# Boostconverter.net
KiCad netlist of a schematic drawn in Altium Designer
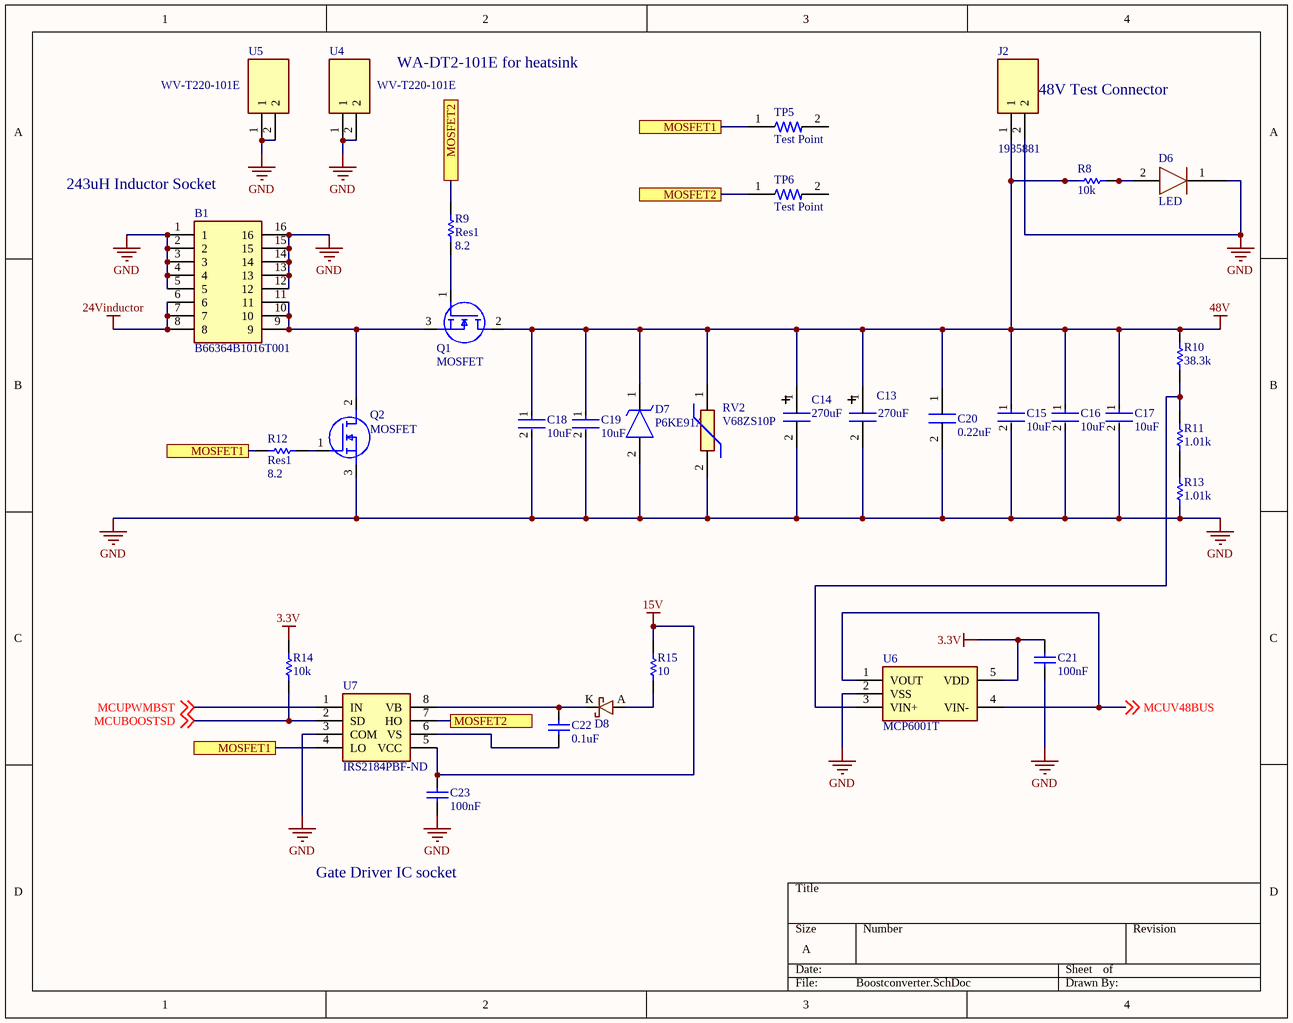
[diagram p0: Boostconverter.SchDoc]

(export (version "E")
  (design (tool "Eeschema 10.0.6"))
  (components
    (comp (ref "B1")
      (value "B66364B1016T001")
      (footprint "B66364B1016T001")
      (description "Bobbin")
      (fields (field (name "MOUSER2 PART NUMBER") "871-B66364B1016T001"))
      (libsource (lib "ee_453_yourname") (part "B66364B1016T001"))
    )
    (comp (ref "C13")
      (value "270uF")
      (footprint "100TXW270MEFC10X50")
      (description "Capacitor, 10mm, 5mm leads")
      (libsource (lib "ee_453_yourname") (part "100TXW270MEFC10X50"))
    )
    (comp (ref "C14")
      (value "270uF")
      (footprint "100TXW270MEFC10X50")
      (description "Capacitor, 10mm, 5mm leads")
      (libsource (lib "ee_453_yourname") (part "100TXW270MEFC10X50"))
    )
    (comp (ref "C15")
      (value "10uF")
      (footprint "FP-CL31-IPC_C")
      (description "Cap Ceramic 220pF 500V C0G ±5% SMD 1206 +125°C Embossed T/R CL31C221JGFNNNF")
      (fields (field (name "TOLERANCE") "5%"))
      (libsource (lib "Altium Content Vault") (part "b4654b650e69147ec39a6b967a45e02"))
    )
    (comp (ref "C16")
      (value "10uF")
      (footprint "FP-CL31-IPC_C")
      (description "Cap Ceramic 220pF 500V C0G ±5% SMD 1206 +125°C Embossed T/R CL31C221JGFNNNF")
      (fields (field (name "TOLERANCE") "5%"))
      (libsource (lib "Altium Content Vault") (part "b4654b650e69147ec39a6b967a45e02"))
    )
    (comp (ref "C17")
      (value "10uF")
      (footprint "FP-CL31-IPC_C")
      (description "Cap Ceramic 220pF 500V C0G ±5% SMD 1206 +125°C Embossed T/R CL31C221JGFNNNF")
      (fields (field (name "TOLERANCE") "5%"))
      (libsource (lib "Altium Content Vault") (part "b4654b650e69147ec39a6b967a45e02"))
    )
    (comp (ref "C18")
      (value "10uF")
      (footprint "FP-CL31-IPC_C")
      (description "Cap Ceramic 220pF 500V C0G ±5% SMD 1206 +125°C Embossed T/R CL31C221JGFNNNF")
      (fields (field (name "TOLERANCE") "5%"))
      (libsource (lib "Altium Content Vault") (part "b4654b650e69147ec39a6b967a45e02"))
    )
    (comp (ref "C19")
      (value "10uF")
      (footprint "FP-CL31-IPC_C")
      (description "Cap Ceramic 220pF 500V C0G ±5% SMD 1206 +125°C Embossed T/R CL31C221JGFNNNF")
      (fields (field (name "TOLERANCE") "5%"))
      (libsource (lib "Altium Content Vault") (part "b4654b650e69147ec39a6b967a45e02"))
    )
    (comp (ref "C20")
      (value "0.22uF")
      (footprint "B32652A3224K000")
      (description "Capacitor, Film, 15mm leads")
      (libsource (lib "ee_453_yourname") (part "B32652A3224K000"))
    )
    (comp (ref "C21")
      (value "100nF")
      (footprint "CAPC1609X100X15LL20")
      (fields
        (field (name "MANUFACTURER") "AVX Interconnect / Elco")
        (field (name "PART NUMBER") "TACL105M006XTA")
      )
      (libsource (lib "Altium Content Vault") (part "CAP"))
    )
    (comp (ref "C22")
      (value "0.1uF")
      (footprint "CAPC1609X100X15LL20")
      (fields
        (field (name "MANUFACTURER") "AVX Interconnect / Elco")
        (field (name "PART NUMBER") "TACL105M006XTA")
      )
      (libsource (lib "Altium Content Vault") (part "CAP"))
    )
    (comp (ref "C23")
      (value "100nF")
      (footprint "CAPC1609X100X15LL20")
      (fields
        (field (name "MANUFACTURER") "AVX Interconnect / Elco")
        (field (name "PART NUMBER") "TACL105M006XTA")
      )
      (libsource (lib "Altium Content Vault") (part "CAP"))
    )
    (comp (ref "D6")
      (value "LED")
      (footprint "LED 0603")
      (description "LED SMD")
      (libsource (lib "ee_453_yourname") (part "LED"))
    )
    (comp (ref "D7")
      (value "P6KE91A")
      (footprint "SamacSys:DIOAD1910W86L670D310")
      (description "TVS Diode (Uni-directional)")
      (fields (field (name "MANUFACTURER_PART_NUMBER") "P6KE91A-E3/54"))
      (libsource (lib "*") (part "P6KE91A-E3_54"))
    )
    (comp (ref "D8")
      (value "SB3H100-E3_54")
      (footprint "SB3H100-E3/54GICT-ND")
      (description "Schottky Diode")
      (libsource (lib "ee_453_yourname") (part "SB3H100-E3_54"))
    )
    (comp (ref "J2")
      (value "1985881")
      (footprint "SamacSys:1985881")
      (description "Connector")
      (fields (field (name "MOUSER PART NUMBER") "651-1985881"))
      (libsource (lib "*") (part "1985881"))
    )
    (comp (ref "Q1")
      (value "MOSFET")
      (footprint "SamacSys:TO254P457X1003X2115-3P")
      (description "MOSFET (N-Channel) IPP200N15N3GXKSA1")
      (fields
        (field (name "MANUFACTURER_PART_NUMBER") "IPP200N15N3GXKSA1")
        (field (name "MOUSER PART NUMBER") "726-IPP200N15N3GXKSA")
      )
      (libsource (lib "*") (part "IPP200N15N3GXKSA1"))
    )
    (comp (ref "Q2")
      (value "MOSFET")
      (footprint "SamacSys:TO254P457X1003X2115-3P")
      (description "MOSFET (N-Channel) IPP200N15N3GXKSA1")
      (fields
        (field (name "MANUFACTURER_PART_NUMBER") "IPP200N15N3GXKSA1")
        (field (name "MOUSER PART NUMBER") "726-IPP200N15N3GXKSA")
      )
      (libsource (lib "*") (part "IPP200N15N3GXKSA1"))
    )
    (comp (ref "R8")
      (value "10k")
      (footprint "RESC1609X50X30NL8T20")
      (description "Chip Resistor, 0 Ohm, Jumper, 100 mW, -55 to 155 degC, 0603 (1608 Metric), RoHS, Tape and Reel")
      (fields (field (name "MANUFACTURER") "Vishay Semiconductor"))
      (libsource (lib "Altium Content Vault") (part "RES-2"))
    )
    (comp (ref "R9")
      (value "Res1")
      (footprint "1210")
      (description "Resistor")
      (fields (field (name "ALTIUM_VALUE") "8.2") (field (name "PUBLISHER") "Altium Limited"))
      (libsource (lib "Miscellaneous Devices") (part "Res1"))
    )
    (comp (ref "R10")
      (value "38.3k")
      (footprint "RESC1609X50X30NL8T20")
      (description "Chip Resistor, 0 Ohm, Jumper, 100 mW, -55 to 155 degC, 0603 (1608 Metric), RoHS, Tape and Reel")
      (fields (field (name "MANUFACTURER") "Vishay Semiconductor"))
      (libsource (lib "Altium Content Vault") (part "RES-2"))
    )
    (comp (ref "R11")
      (value "1.01k")
      (footprint "RESC1609X50X30NL8T20")
      (description "Chip Resistor, 0 Ohm, Jumper, 100 mW, -55 to 155 degC, 0603 (1608 Metric), RoHS, Tape and Reel")
      (fields (field (name "MANUFACTURER") "Vishay Semiconductor"))
      (libsource (lib "Altium Content Vault") (part "RES-2"))
    )
    (comp (ref "R12")
      (value "Res1")
      (footprint "1210")
      (description "Resistor")
      (fields (field (name "ALTIUM_VALUE") "8.2") (field (name "PUBLISHER") "Altium Limited"))
      (libsource (lib "Miscellaneous Devices") (part "Res1"))
    )
    (comp (ref "R13")
      (value "1.01k")
      (footprint "RESC1609X50X30NL8T20")
      (description "Chip Resistor, 0 Ohm, Jumper, 100 mW, -55 to 155 degC, 0603 (1608 Metric), RoHS, Tape and Reel")
      (fields (field (name "MANUFACTURER") "Vishay Semiconductor"))
      (libsource (lib "Altium Content Vault") (part "RES-2"))
    )
    (comp (ref "R14")
      (value "10k")
      (footprint "RESC1609X50X30NL8T20")
      (description "Chip Resistor, 0 Ohm, Jumper, 100 mW, -55 to 155 degC, 0603 (1608 Metric), RoHS, Tape and Reel")
      (fields (field (name "MANUFACTURER") "Vishay Semiconductor"))
      (libsource (lib "Altium Content Vault") (part "RES-2"))
    )
    (comp (ref "R15")
      (value "10")
      (footprint "RESC1609X50X30NL8T20")
      (description "Chip Resistor, 0 Ohm, Jumper, 100 mW, -55 to 155 degC, 0603 (1608 Metric), RoHS, Tape and Reel")
      (fields (field (name "MANUFACTURER") "Vishay Semiconductor"))
      (libsource (lib "Altium Content Vault") (part "RES-2"))
    )
    (comp (ref "RV2")
      (value "V68ZS10P")
      (footprint "SamacSys:V68ZS10P")
      (description "Varistor")
      (fields (field (name "MOUSER PART NUMBER") "576-V68ZS10P"))
      (libsource (lib "*") (part "V68ZS10P"))
    )
    (comp (ref "TP5")
      (value "Test Point")
      (footprint "RESC3216X70N")
      (description "PC Test Point , Plating Surface Mount Mounting Type")
      (fields (field (name "MF") "KOA Speer") (field (name "MP") "RCWCTE"))
      (libsource (lib "SnapEDAsch") (part "RCWCTE"))
    )
    (comp (ref "TP6")
      (value "Test Point")
      (footprint "RESC3216X70N")
      (description "PC Test Point , Plating Surface Mount Mounting Type")
      (fields (field (name "MF") "KOA Speer") (field (name "MP") "RCWCTE"))
      (libsource (lib "SnapEDAsch") (part "RCWCTE"))
    )
    (comp (ref "U4")
      (value "WV-T220-101E")
      (footprint "SamacSys:WVT220101E")
      (description "Undefined or Miscellaneous")
      (fields (field (name "MOUSER PART NUMBER") "588-WV-T220-101E"))
      (libsource (lib "*") (part "WV-T220-101E"))
    )
    (comp (ref "U5")
      (value "WV-T220-101E")
      (footprint "SamacSys:WVT220101E")
      (description "Undefined or Miscellaneous")
      (fields (field (name "MOUSER PART NUMBER") "588-WV-T220-101E"))
      (libsource (lib "*") (part "WV-T220-101E"))
    )
    (comp (ref "U6")
      (value "MCP6001T")
      (footprint "SOT-23")
      (description "Op-Amp")
      (libsource (lib "ee_453_yourname") (part "MCP6001T"))
    )
    (comp (ref "U7")
      (value "IRS2184PBF-ND")
      (footprint "DIP8")
      (description "Boost Driver")
      (fields
        (field (name "MOUSER2 PART NUMBER") "649-DILB8P223TLF")
        (field (name "MANUFACTURER_PART_NUMBER") "DILB8P-223TLF")
      )
      (libsource (lib "ee_453_yourname") (part "IRS2184PBF-ND"))
    )
  )
  (nets
    (net (code "1") (name "/MOSFET1") (class "Default")
      (node (ref "R12") (pin "2") (pinfunction "2_2") (pintype "passive"))
      (node (ref "TP5") (pin "1") (pinfunction "1_1") (pintype "passive"))
      (node (ref "U7") (pin "4") (pinfunction "LO_4") (pintype "passive"))
    )
    (net (code "2") (name "/MOSFET2") (class "Default")
      (node (ref "R9") (pin "2") (pinfunction "2_2") (pintype "passive"))
      (node (ref "TP6") (pin "1") (pinfunction "1_1") (pintype "passive"))
      (node (ref "U7") (pin "7") (pinfunction "HO_7") (pintype "passive"))
    )
    (net (code "3") (name "3.3V") (class "Default")
      (node (ref "C21") (pin "1") (pinfunction "1_1") (pintype "passive"))
      (node (ref "R14") (pin "2") (pinfunction "2_2") (pintype "passive"))
      (node (ref "U6") (pin "5") (pinfunction "VDD_5") (pintype "passive"))
    )
    (net (code "4") (name "15V") (class "Default")
      (node (ref "C23") (pin "2") (pinfunction "2_2") (pintype "passive"))
      (node (ref "R15") (pin "2") (pinfunction "2_2") (pintype "passive"))
      (node (ref "U7") (pin "5") (pinfunction "VCC_5") (pintype "passive"))
    )
    (net (code "5") (name "24Vinductor") (class "Default")
      (node (ref "B1") (pin "6") (pinfunction "6_6") (pintype "passive"))
      (node (ref "B1") (pin "7") (pinfunction "7_7") (pintype "passive"))
      (node (ref "B1") (pin "8") (pinfunction "8_8") (pintype "passive"))
    )
    (net (code "6") (name "48V") (class "Default")
      (node (ref "C13") (pin "1") (pintype "passive"))
      (node (ref "C14") (pin "1") (pintype "passive"))
      (node (ref "C15") (pin "1") (pinfunction "1_1") (pintype "passive"))
      (node (ref "C16") (pin "1") (pinfunction "1_1") (pintype "passive"))
      (node (ref "C17") (pin "1") (pinfunction "1_1") (pintype "passive"))
      (node (ref "C18") (pin "1") (pinfunction "1_1") (pintype "passive"))
      (node (ref "C19") (pin "1") (pinfunction "1_1") (pintype "passive"))
      (node (ref "C20") (pin "1") (pintype "passive"))
      (node (ref "D7") (pin "1") (pinfunction "K_1") (pintype "passive"))
      (node (ref "J2") (pin "1") (pinfunction "1_1") (pintype "passive"))
      (node (ref "Q1") (pin "2") (pinfunction "D_2") (pintype "passive"))
      (node (ref "R10") (pin "2") (pinfunction "2_2") (pintype "passive"))
      (node (ref "R8") (pin "1") (pinfunction "1_1") (pintype "passive"))
      (node (ref "RV2") (pin "1") (pinfunction "1_1") (pintype "passive"))
    )
    (net (code "7") (name "GND") (class "Default")
      (node (ref "B1") (pin "1") (pinfunction "1_1") (pintype "passive"))
      (node (ref "B1") (pin "12") (pinfunction "12_12") (pintype "passive"))
      (node (ref "B1") (pin "13") (pinfunction "13_13") (pintype "passive"))
      (node (ref "B1") (pin "14") (pinfunction "14_14") (pintype "passive"))
      (node (ref "B1") (pin "15") (pinfunction "15_15") (pintype "passive"))
      (node (ref "B1") (pin "16") (pinfunction "16_16") (pintype "passive"))
      (node (ref "B1") (pin "2") (pinfunction "2_2") (pintype "passive"))
      (node (ref "B1") (pin "3") (pinfunction "3_3") (pintype "passive"))
      (node (ref "B1") (pin "4") (pinfunction "4_4") (pintype "passive"))
      (node (ref "B1") (pin "5") (pinfunction "5_5") (pintype "passive"))
      (node (ref "C13") (pin "2") (pintype "passive"))
      (node (ref "C14") (pin "2") (pintype "passive"))
      (node (ref "C15") (pin "2") (pinfunction "2_2") (pintype "passive"))
      (node (ref "C16") (pin "2") (pinfunction "2_2") (pintype "passive"))
      (node (ref "C17") (pin "2") (pinfunction "2_2") (pintype "passive"))
      (node (ref "C18") (pin "2") (pinfunction "2_2") (pintype "passive"))
      (node (ref "C19") (pin "2") (pinfunction "2_2") (pintype "passive"))
      (node (ref "C20") (pin "2") (pintype "passive"))
      (node (ref "C21") (pin "2") (pinfunction "2_2") (pintype "passive"))
      (node (ref "C23") (pin "1") (pinfunction "1_1") (pintype "passive"))
      (node (ref "D6") (pin "1") (pintype "passive"))
      (node (ref "D7") (pin "2") (pinfunction "A_2") (pintype "passive"))
      (node (ref "J2") (pin "2") (pinfunction "2_2") (pintype "passive"))
      (node (ref "Q2") (pin "3") (pinfunction "S_3") (pintype "passive"))
      (node (ref "R13") (pin "1") (pinfunction "1_1") (pintype "passive"))
      (node (ref "RV2") (pin "2") (pinfunction "2_2") (pintype "passive"))
      (node (ref "U4") (pin "1") (pinfunction "1_1") (pintype "passive"))
      (node (ref "U4") (pin "2") (pinfunction "2_2") (pintype "passive"))
      (node (ref "U5") (pin "1") (pinfunction "1_1") (pintype "passive"))
      (node (ref "U5") (pin "2") (pinfunction "2_2") (pintype "passive"))
      (node (ref "U6") (pin "2") (pinfunction "VSS_2") (pintype "passive"))
      (node (ref "U7") (pin "3") (pinfunction "COM_3") (pintype "passive"))
    )
    (net (code "8") (name "MCUBOOSTSD") (class "Default")
      (node (ref "R14") (pin "1") (pinfunction "1_1") (pintype "passive"))
      (node (ref "U7") (pin "2") (pinfunction "SD_2") (pintype "passive"))
    )
    (net (code "9") (name "MCUPWMBST") (class "Default")
      (node (ref "U7") (pin "1") (pinfunction "IN_1") (pintype "passive"))
    )
    (net (code "10") (name "MCUV48BUS") (class "Default")
      (node (ref "U6") (pin "1") (pinfunction "VOUT_1") (pintype "passive"))
      (node (ref "U6") (pin "4") (pinfunction "VIN-_4") (pintype "passive"))
    )
    (net (code "11") (name "Net-(D6-Pad2)") (class "Default")
      (node (ref "D6") (pin "2") (pintype "passive"))
      (node (ref "R8") (pin "2") (pinfunction "2_2") (pintype "passive"))
    )
    (net (code "12") (name "Net-(D8-PadA)") (class "Default")
      (node (ref "D8") (pin "A") (pintype "passive"))
      (node (ref "R15") (pin "1") (pinfunction "1_1") (pintype "passive"))
    )
    (net (code "13") (name "Net-(Q1-G)") (class "Default")
      (node (ref "Q1") (pin "1") (pinfunction "G_1") (pintype "passive"))
      (node (ref "R9") (pin "1") (pinfunction "1_1") (pintype "passive"))
    )
    (net (code "14") (name "Net-(Q1-S)") (class "Default")
      (node (ref "B1") (pin "10") (pinfunction "10_10") (pintype "passive"))
      (node (ref "B1") (pin "11") (pinfunction "11_11") (pintype "passive"))
      (node (ref "B1") (pin "9") (pinfunction "9_9") (pintype "passive"))
      (node (ref "Q1") (pin "3") (pinfunction "S_3") (pintype "passive"))
      (node (ref "Q2") (pin "2") (pinfunction "D_2") (pintype "passive"))
    )
    (net (code "15") (name "Net-(Q2-G)") (class "Default")
      (node (ref "Q2") (pin "1") (pinfunction "G_1") (pintype "passive"))
      (node (ref "R12") (pin "1") (pinfunction "1_1") (pintype "passive"))
    )
    (net (code "16") (name "Net-(R11-Pad1)") (class "Default")
      (node (ref "R11") (pin "1") (pinfunction "1_1") (pintype "passive"))
      (node (ref "R13") (pin "2") (pinfunction "2_2") (pintype "passive"))
    )
    (net (code "17") (name "Net-(U6-VIN+)") (class "Default")
      (node (ref "R10") (pin "1") (pinfunction "1_1") (pintype "passive"))
      (node (ref "R11") (pin "2") (pinfunction "2_2") (pintype "passive"))
      (node (ref "U6") (pin "3") (pinfunction "VIN+_3") (pintype "passive"))
    )
    (net (code "18") (name "Net-(U7-VB)") (class "Default")
      (node (ref "C22") (pin "2") (pinfunction "2_2") (pintype "passive"))
      (node (ref "D8") (pin "K") (pintype "passive"))
      (node (ref "U7") (pin "8") (pinfunction "VB_8") (pintype "passive"))
    )
    (net (code "19") (name "Net-(U7-VS)") (class "Default")
      (node (ref "C22") (pin "1") (pinfunction "1_1") (pintype "passive"))
      (node (ref "U7") (pin "6") (pinfunction "VS_6") (pintype "passive"))
    )
    (net (code "20") (name "unconnected-(TP5-Pad2)") (class "Default")
      (node (ref "TP5") (pin "2") (pinfunction "2_2") (pintype "passive"))
    )
    (net (code "21") (name "unconnected-(TP6-Pad2)") (class "Default")
      (node (ref "TP6") (pin "2") (pinfunction "2_2") (pintype "passive"))
    )
  )
)
